# Main.net
KiCad netlist of a schematic drawn in Altium Designer
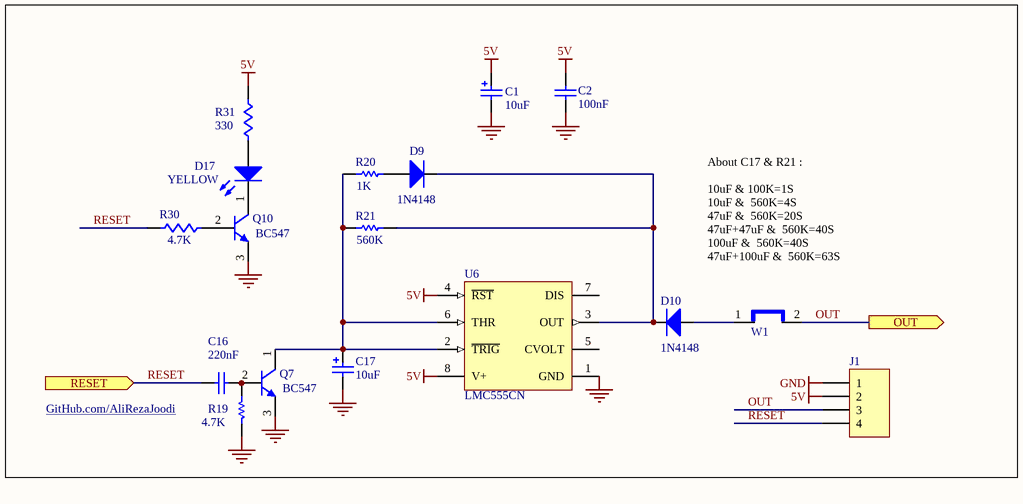
[diagram p0: Main.SchDoc]

(export (version "E")
  (design (tool "Eeschema 10.0.6"))
  (components
    (comp (ref "C1")
      (value "10uF")
      (footprint "CAPPR2.5-6.3x5")
      (description "Polarized Capacitor (Radial)")
      (fields (field (name "MANUFACTURER") "Generic Components") (field (name "PUBLISHER") "Altium Limited"))
      (libsource (lib "Miscellaneous Devices") (part "Cap Pol1"))
    )
    (comp (ref "C2")
      (value "100nF")
      (footprint "CAPNTO2.54-3.56x2.03")
      (description "Capacitor")
      (fields (field (name "PUBLISHER") "Altium Limited"))
      (libsource (lib "Miscellaneous Devices") (part "Cap"))
    )
    (comp (ref "C16")
      (value "220nF")
      (footprint "CAPNTO5.08-7.37x3.94")
      (description "Capacitor")
      (fields (field (name "PUBLISHER") "Altium Limited"))
      (libsource (lib "Miscellaneous Devices") (part "Cap"))
    )
    (comp (ref "C17")
      (value "10uF")
      (footprint "CAPPR2.5-6.3x5")
      (description "Polarized Capacitor (Radial)")
      (fields (field (name "MANUFACTURER") "Generic Components") (field (name "PUBLISHER") "Altium Limited"))
      (libsource (lib "Miscellaneous Devices") (part "Cap Pol1"))
    )
    (comp (ref "D9")
      (value "1N4148")
      (footprint "DIODE0.4_Glass")
      (description "Default Diode")
      (fields (field (name "MANUFACTURER") "Generic Components") (field (name "PUBLISHER") "Altium Limited"))
      (libsource (lib "Miscellaneous Devices") (part "Diode"))
    )
    (comp (ref "D10")
      (value "1N4148")
      (footprint "DIODE0.4_Glass")
      (description "Default Diode")
      (fields (field (name "MANUFACTURER") "Generic Components") (field (name "PUBLISHER") "Altium Limited"))
      (libsource (lib "Miscellaneous Devices") (part "Diode"))
    )
    (comp (ref "D17")
      (value "YELLOW")
      (footprint "LED-5mm_Red")
      (description "Typical INFRARED GaAs LED")
      (fields (field (name "MANUFACTURER") "Generic Components") (field (name "PUBLISHER") "Altium Limited"))
      (libsource (lib "Miscellaneous Devices") (part "LED"))
    )
    (comp (ref "J1")
      (value "4PIN")
      (footprint "HDR1X4")
      (description "Header, 4-Pin")
      (fields (field (name "MANUFACTURER") "Generic Components") (field (name "PUBLISHER") "Altium Limited"))
      (libsource (lib "Miscellaneous Connectors") (part "Header 4"))
    )
    (comp (ref "Q7")
      (value "BC547")
      (footprint "TO92C")
      (description "NPN Bipolar Transistor")
      (fields (field (name "MANUFACTURER") "Generic Components") (field (name "PUBLISHER") "Altium Limited"))
      (libsource (lib "Miscellaneous Devices") (part "NPN"))
    )
    (comp (ref "Q10")
      (value "BC547")
      (footprint "TO92C")
      (description "NPN Bipolar Transistor")
      (fields (field (name "MANUFACTURER") "Generic Components") (field (name "PUBLISHER") "Altium Limited"))
      (libsource (lib "Miscellaneous Devices") (part "NPN"))
    )
    (comp (ref "R19")
      (value "4.7K")
      (footprint "AXIAL-0.4")
      (description "Resistor")
      (fields (field (name "PUBLISHER") "Altium Limited"))
      (libsource (lib "Miscellaneous Devices") (part "Res1"))
    )
    (comp (ref "R20")
      (value "1K")
      (footprint "AXIAL-0.4")
      (description "Resistor")
      (fields (field (name "PUBLISHER") "Altium Limited"))
      (libsource (lib "Miscellaneous Devices") (part "Res1"))
    )
    (comp (ref "R21")
      (value "560K")
      (footprint "AXIAL-0.4")
      (description "Resistor")
      (fields (field (name "PUBLISHER") "Altium Limited"))
      (libsource (lib "Miscellaneous Devices") (part "Res1"))
    )
    (comp (ref "R30")
      (value "4.7K")
      (footprint "AXIAL-0.4")
      (description "Resistor")
      (fields (field (name "MANUFACTURER") "Generic Components") (field (name "PUBLISHER") "Altium Limited"))
      (libsource (lib "") (part "Res1_1"))
    )
    (comp (ref "R31")
      (value "330")
      (footprint "AXIAL-0.4")
      (description "Resistor")
      (fields (field (name "MANUFACTURER") "Generic Components") (field (name "PUBLISHER") "Altium Limited"))
      (libsource (lib "") (part "Res1_1"))
    )
    (comp (ref "U6")
      (value "LMC555CN")
      (footprint "N08E")
      (description "CMOS Timer, 8-pin MDIP")
      (fields
        (field (name "MANUFACTURER") "National Semiconductor")
        (field (name "PUBLISHER") "Altium Limited")
      )
      (libsource (lib "NSC Analog") (part "LMC555CN"))
    )
    (comp (ref "W1")
      (value "Jumper")
      (footprint "PIN2")
      (description "Jumper Wire")
      (fields (field (name "MANUFACTURER") "Generic Components") (field (name "PUBLISHER") "Altium Limited"))
      (libsource (lib "my Libraries") (part "Jumper 2pin_2"))
    )
  )
  (nets
    (net (code "1") (name "/OUT") (class "Default")
      (node (ref "J1") (pin "3") (pinfunction "3_3") (pintype "passive"))
      (node (ref "W1") (pin "2") (pinfunction "2_2") (pintype "passive"))
    )
    (net (code "2") (name "/RESET") (class "Default")
      (node (ref "C16") (pin "1") (pinfunction "1_1") (pintype "passive"))
      (node (ref "J1") (pin "4") (pinfunction "4_4") (pintype "passive"))
      (node (ref "R30") (pin "1") (pinfunction "1_1") (pintype "passive"))
    )
    (net (code "3") (name "5V") (class "Default")
      (node (ref "C1") (pin "1") (pinfunction "1_1") (pintype "passive"))
      (node (ref "C2") (pin "2") (pinfunction "2_2") (pintype "passive"))
      (node (ref "J1") (pin "2") (pinfunction "2_2") (pintype "passive"))
      (node (ref "R31") (pin "1") (pinfunction "1_1") (pintype "passive"))
      (node (ref "U6") (pin "4") (pinfunction "~{RST}_4") (pintype "input"))
      (node (ref "U6") (pin "8") (pinfunction "V+_8") (pintype "power_in"))
    )
    (net (code "4") (name "GND") (class "Default")
      (node (ref "C1") (pin "2") (pinfunction "2_2") (pintype "passive"))
      (node (ref "C17") (pin "2") (pinfunction "2_2") (pintype "passive"))
      (node (ref "C2") (pin "1") (pinfunction "1_1") (pintype "passive"))
      (node (ref "J1") (pin "1") (pinfunction "1_1") (pintype "passive"))
      (node (ref "Q10") (pin "3") (pinfunction "E_3") (pintype "passive"))
      (node (ref "Q7") (pin "3") (pinfunction "E_3") (pintype "passive"))
      (node (ref "R19") (pin "2") (pinfunction "2_2") (pintype "passive"))
      (node (ref "U6") (pin "1") (pinfunction "GND_1") (pintype "power_in"))
    )
    (net (code "5") (name "Net-(D9-A)") (class "Default")
      (node (ref "D9") (pin "1") (pinfunction "A_1") (pintype "passive"))
      (node (ref "R20") (pin "2") (pinfunction "2_2") (pintype "passive"))
    )
    (net (code "6") (name "Net-(D10-A)") (class "Default")
      (node (ref "D10") (pin "1") (pinfunction "A_1") (pintype "passive"))
      (node (ref "W1") (pin "1") (pinfunction "1_1") (pintype "passive"))
    )
    (net (code "7") (name "Net-(D10-K)") (class "Default")
      (node (ref "D10") (pin "2") (pinfunction "K_2") (pintype "passive"))
      (node (ref "D9") (pin "2") (pinfunction "K_2") (pintype "passive"))
      (node (ref "R21") (pin "2") (pinfunction "2_2") (pintype "passive"))
      (node (ref "U6") (pin "3") (pinfunction "OUT_3") (pintype "output"))
    )
    (net (code "8") (name "Net-(D17-A)") (class "Default")
      (node (ref "D17") (pin "1") (pinfunction "A_1") (pintype "passive"))
      (node (ref "R31") (pin "2") (pinfunction "2_2") (pintype "passive"))
    )
    (net (code "9") (name "Net-(D17-K)") (class "Default")
      (node (ref "D17") (pin "2") (pinfunction "K_2") (pintype "passive"))
      (node (ref "Q10") (pin "1") (pinfunction "C_1") (pintype "passive"))
    )
    (net (code "10") (name "Net-(Q7-B)") (class "Default")
      (node (ref "C16") (pin "2") (pinfunction "2_2") (pintype "passive"))
      (node (ref "Q7") (pin "2") (pinfunction "B_2") (pintype "passive"))
      (node (ref "R19") (pin "1") (pinfunction "1_1") (pintype "passive"))
    )
    (net (code "11") (name "Net-(Q7-C)") (class "Default")
      (node (ref "C17") (pin "1") (pinfunction "1_1") (pintype "passive"))
      (node (ref "Q7") (pin "1") (pinfunction "C_1") (pintype "passive"))
      (node (ref "R20") (pin "1") (pinfunction "1_1") (pintype "passive"))
      (node (ref "R21") (pin "1") (pinfunction "1_1") (pintype "passive"))
      (node (ref "U6") (pin "2") (pinfunction "~{TRIG}_2") (pintype "input"))
      (node (ref "U6") (pin "6") (pinfunction "THR_6") (pintype "input"))
    )
    (net (code "12") (name "Net-(Q10-B)") (class "Default")
      (node (ref "Q10") (pin "2") (pinfunction "B_2") (pintype "passive"))
      (node (ref "R30") (pin "2") (pinfunction "2_2") (pintype "passive"))
    )
    (net (code "13") (name "unconnected-(U6-CVOLT-Pad5)") (class "Default")
      (node (ref "U6") (pin "5") (pinfunction "CVOLT_5") (pintype "passive"))
    )
    (net (code "14") (name "unconnected-(U6-DIS-Pad7)") (class "Default")
      (node (ref "U6") (pin "7") (pinfunction "DIS_7") (pintype "open_collector"))
    )
  )
)
